# STWD100_Charger_Controller_rev1.net
KiCad netlist of a schematic drawn in EAGLE
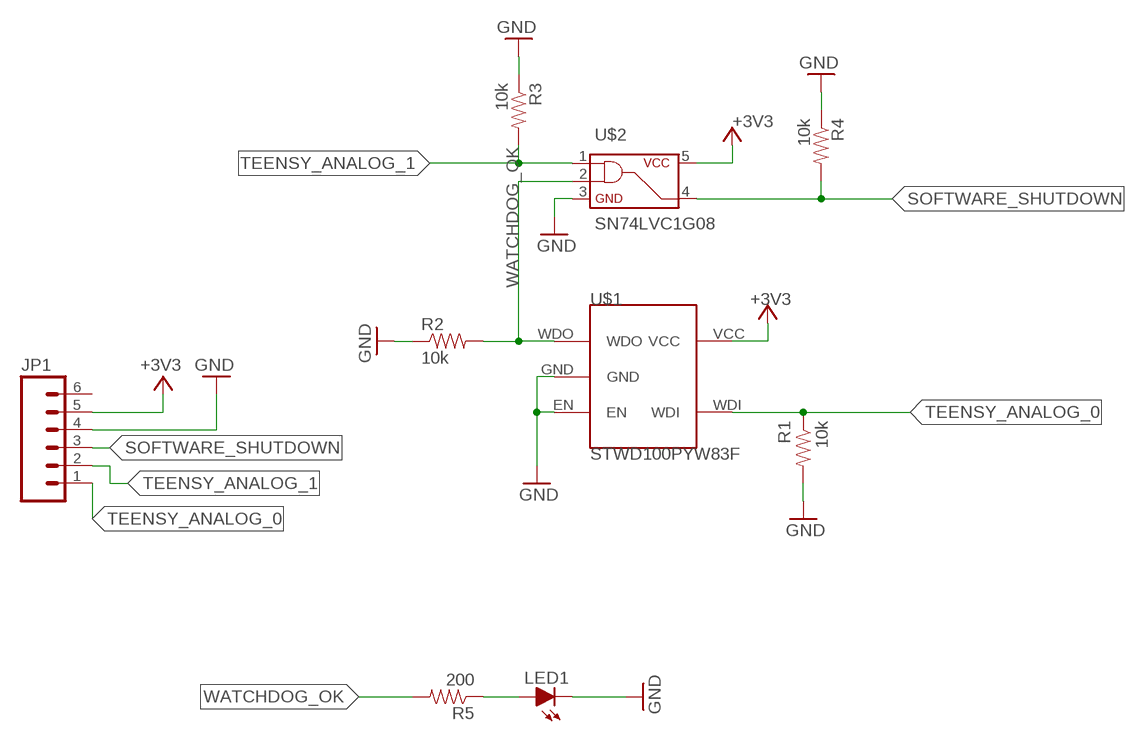
[diagram p0: schematic, sheet 1]

(export (version "E")
  (design (tool "Eeschema 10.0.6"))
  (components
    (comp (ref "JP1")
      (value "M06")
      (footprint "eagle-import:1X06")
      (libsource (lib "eagle-import") (part "M06"))
    )
    (comp (ref "LED1")
      (value "LED-0603")
      (footprint "eagle-import:LED-603")
      (libsource (lib "eagle-import") (part "LED-0603"))
    )
    (comp (ref "R1")
      (value "10k")
      (footprint "eagle-import:0603-RES")
      (libsource (lib "eagle-import") (part "RESISTOR0603-RES"))
    )
    (comp (ref "R2")
      (value "10k")
      (footprint "eagle-import:0603-RES")
      (libsource (lib "eagle-import") (part "RESISTOR0603-RES"))
    )
    (comp (ref "R3")
      (value "10k")
      (footprint "eagle-import:0603-RES")
      (libsource (lib "eagle-import") (part "RESISTOR0603-RES"))
    )
    (comp (ref "R4")
      (value "10k")
      (footprint "eagle-import:0603-RES")
      (libsource (lib "eagle-import") (part "RESISTOR0603-RES"))
    )
    (comp (ref "R5")
      (value "200")
      (footprint "eagle-import:0603-RES")
      (libsource (lib "eagle-import") (part "RESISTOR0603-RES"))
    )
    (comp (ref "U$1")
      (value "STWD100PYW83F")
      (footprint "eagle-import:SOT323-5")
      (libsource (lib "eagle-import") (part "STWD100PYW83F"))
    )
    (comp (ref "U$2")
      (value "SN74LVC1G08")
      (footprint "eagle-import:SOT-23-5")
      (libsource (lib "eagle-import") (part "SN74LVC1G08"))
    )
  )
  (nets
    (net (code "1") (name "+3V3") (class "Default")
      (node (ref "JP1") (pin "5") (pinfunction "5_5") (pintype "passive"))
      (node (ref "U$1") (pin "VCC") (pinfunction "VCC_VCC") (pintype "bidirectional"))
      (node (ref "U$2") (pin "5") (pinfunction "5_5") (pintype "passive"))
    )
    (net (code "2") (name "GND") (class "Default")
      (node (ref "JP1") (pin "4") (pinfunction "4_4") (pintype "passive"))
      (node (ref "LED1") (pin "C") (pinfunction "C_C") (pintype "passive"))
      (node (ref "R1") (pin "2") (pinfunction "2_2") (pintype "passive"))
      (node (ref "R2") (pin "1") (pinfunction "1_1") (pintype "passive"))
      (node (ref "R3") (pin "1") (pinfunction "1_1") (pintype "passive"))
      (node (ref "R4") (pin "1") (pinfunction "1_1") (pintype "passive"))
      (node (ref "U$1") (pin "EN") (pinfunction "EN_EN") (pintype "bidirectional"))
      (node (ref "U$1") (pin "GND") (pinfunction "GND_GND") (pintype "bidirectional"))
      (node (ref "U$2") (pin "3") (pinfunction "3_3") (pintype "passive"))
    )
    (net (code "3") (name "Net-(LED1-PadA)") (class "Default")
      (node (ref "LED1") (pin "A") (pinfunction "A_A") (pintype "passive"))
      (node (ref "R5") (pin "1") (pinfunction "1_1") (pintype "passive"))
    )
    (net (code "4") (name "SOFTWARE_SHUTDOWN") (class "Default")
      (node (ref "JP1") (pin "3") (pinfunction "3_3") (pintype "passive"))
      (node (ref "R4") (pin "2") (pinfunction "2_2") (pintype "passive"))
      (node (ref "U$2") (pin "4") (pinfunction "4_4") (pintype "passive"))
    )
    (net (code "5") (name "TEENSY_ANALOG_0") (class "Default")
      (node (ref "JP1") (pin "1") (pinfunction "1_1") (pintype "passive"))
      (node (ref "R1") (pin "1") (pinfunction "1_1") (pintype "passive"))
      (node (ref "U$1") (pin "WDI") (pinfunction "WDI_WDI") (pintype "bidirectional"))
    )
    (net (code "6") (name "TEENSY_ANALOG_1") (class "Default")
      (node (ref "JP1") (pin "2") (pinfunction "2_2") (pintype "passive"))
      (node (ref "R3") (pin "2") (pinfunction "2_2") (pintype "passive"))
      (node (ref "U$2") (pin "1") (pinfunction "1_1") (pintype "passive"))
    )
    (net (code "7") (name "WATCHDOG_OK") (class "Default")
      (node (ref "R2") (pin "2") (pinfunction "2_2") (pintype "passive"))
      (node (ref "R5") (pin "2") (pinfunction "2_2") (pintype "passive"))
      (node (ref "U$1") (pin "WDO") (pinfunction "WDO_WDO") (pintype "bidirectional"))
      (node (ref "U$2") (pin "2") (pinfunction "2_2") (pintype "passive"))
    )
    (net (code "8") (name "unconnected-(JP1-Pad6)") (class "Default")
      (node (ref "JP1") (pin "6") (pinfunction "6_6") (pintype "passive"))
    )
  )
)
